# nrf_can.net
KiCad netlist of a schematic drawn in EAGLE
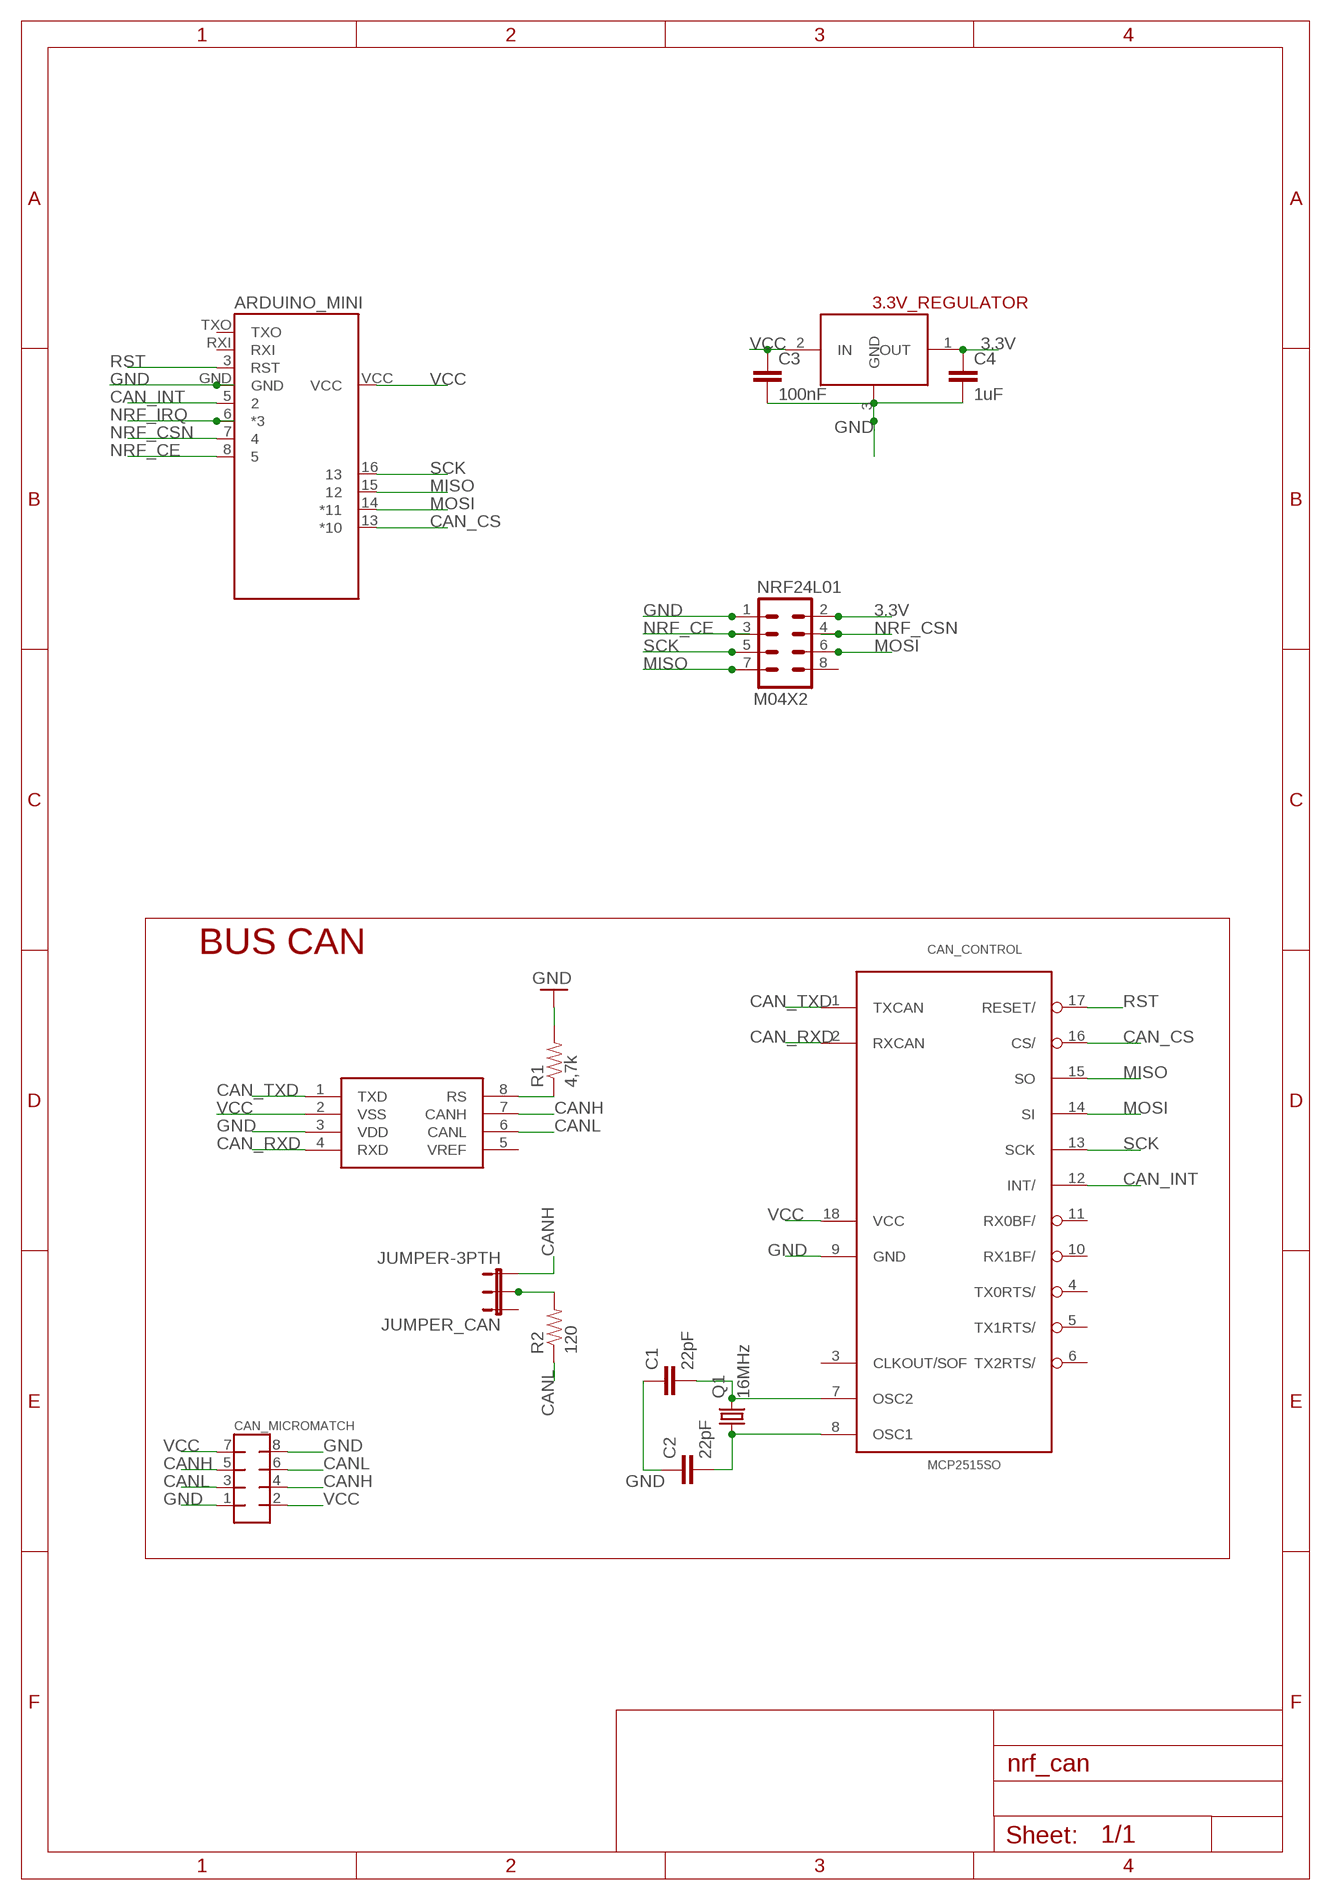
[diagram p0: schematic, sheet 1]

(export (version "E")
  (design (tool "Eeschema 10.0.6"))
  (components
    (comp (ref "3.3V_REGULATOR")
      (value "LM3480IM4")
      (footprint "eagle-import:SOT23-3")
      (libsource (lib "eagle-import") (part "LM3480IM4"))
    )
    (comp (ref "ARDUINO_MINI")
      (value "ARDUINO_PRO_MININRF24L01")
      (footprint "eagle-import:ARDUINO_PRO_MINI")
      (libsource (lib "eagle-import") (part "ARDUINO_PRO_MININRF24L01"))
    )
    (comp (ref "C1")
      (value "22pF")
      (footprint "eagle-import:0805")
      (libsource (lib "eagle-import") (part "CAP0805"))
    )
    (comp (ref "C2")
      (value "22pF")
      (footprint "eagle-import:0805")
      (libsource (lib "eagle-import") (part "CAP0805"))
    )
    (comp (ref "C3")
      (value "100nF")
      (footprint "eagle-import:0805")
      (libsource (lib "eagle-import") (part "CAP0805"))
    )
    (comp (ref "C4")
      (value "1uF")
      (footprint "eagle-import:0805")
      (libsource (lib "eagle-import") (part "CAP0805"))
    )
    (comp (ref "CAN_CONTROL")
      (value "MCP2515SO")
      (footprint "eagle-import:SO18L")
      (libsource (lib "eagle-import") (part "MCP2515SO"))
    )
    (comp (ref "CAN_MICROMATCH")
      (value "MMATCH-8-PTH")
      (footprint "eagle-import:AMP-215079-8")
      (libsource (lib "eagle-import") (part "MMATCH-8-PTH"))
    )
    (comp (ref "JUMPER_CAN")
      (value "JUMPER-3PTH")
      (footprint "eagle-import:1X03")
      (libsource (lib "eagle-import") (part "JUMPER-3PTH"))
    )
    (comp (ref "NRF24L01")
      (value "M04X2")
      (footprint "eagle-import:2X4")
      (libsource (lib "eagle-import") (part "M04X2"))
    )
    (comp (ref "Q1")
      (value "16MHz")
      (footprint "eagle-import:HC49_S")
      (libsource (lib "eagle-import") (part "CRYSTALHC49S"))
    )
    (comp (ref "R1")
      (value "4,7k")
      (footprint "eagle-import:0805")
      (libsource (lib "eagle-import") (part "RESISTOR0805-RES"))
    )
    (comp (ref "R2")
      (value "120")
      (footprint "eagle-import:0805")
      (libsource (lib "eagle-import") (part "RESISTOR0805-RES"))
    )
    (comp (ref "TRANSCEIVER")
      (value "MCP2551")
      (footprint "eagle-import:SO08")
      (libsource (lib "eagle-import") (part "MCP2551"))
    )
  )
  (nets
    (net (code "1") (name "/3.3V") (class "Default")
      (node (ref "3.3V_REGULATOR") (pin "1") (pinfunction "OUT_1") (pintype "bidirectional"))
      (node (ref "C4") (pin "1") (pinfunction "1_1") (pintype "passive"))
      (node (ref "NRF24L01") (pin "2") (pinfunction "2_2") (pintype "passive"))
    )
    (net (code "2") (name "/CANH") (class "Default")
      (node (ref "CAN_MICROMATCH") (pin "4") (pinfunction "4_4") (pintype "bidirectional"))
      (node (ref "CAN_MICROMATCH") (pin "5") (pinfunction "5_5") (pintype "bidirectional"))
      (node (ref "JUMPER_CAN") (pin "3") (pinfunction "3_3") (pintype "passive"))
      (node (ref "TRANSCEIVER") (pin "7") (pinfunction "CANH_7") (pintype "bidirectional"))
    )
    (net (code "3") (name "/CANL") (class "Default")
      (node (ref "CAN_MICROMATCH") (pin "3") (pinfunction "3_3") (pintype "bidirectional"))
      (node (ref "CAN_MICROMATCH") (pin "6") (pinfunction "6_6") (pintype "bidirectional"))
      (node (ref "R2") (pin "1") (pinfunction "1_1") (pintype "passive"))
      (node (ref "TRANSCEIVER") (pin "6") (pinfunction "CANL_6") (pintype "bidirectional"))
    )
    (net (code "4") (name "/CAN_CS") (class "Default")
      (node (ref "ARDUINO_MINI") (pin "13") (pinfunction "*10_13") (pintype "bidirectional"))
      (node (ref "CAN_CONTROL") (pin "16") (pinfunction "CS/_16") (pintype "input"))
    )
    (net (code "5") (name "/CAN_INT") (class "Default")
      (node (ref "ARDUINO_MINI") (pin "5") (pinfunction "2_5") (pintype "bidirectional"))
      (node (ref "CAN_CONTROL") (pin "12") (pinfunction "INT/_12") (pintype "output"))
    )
    (net (code "6") (name "/CAN_RXD") (class "Default")
      (node (ref "CAN_CONTROL") (pin "2") (pinfunction "RXCAN_2") (pintype "input"))
      (node (ref "TRANSCEIVER") (pin "4") (pinfunction "RXD_4") (pintype "bidirectional"))
    )
    (net (code "7") (name "/CAN_TXD") (class "Default")
      (node (ref "CAN_CONTROL") (pin "1") (pinfunction "TXCAN_1") (pintype "output"))
      (node (ref "TRANSCEIVER") (pin "1") (pinfunction "TXD_1") (pintype "bidirectional"))
    )
    (net (code "8") (name "/MISO") (class "Default")
      (node (ref "ARDUINO_MINI") (pin "15") (pinfunction "12_15") (pintype "bidirectional"))
      (node (ref "CAN_CONTROL") (pin "15") (pinfunction "SO_15") (pintype "output"))
      (node (ref "NRF24L01") (pin "7") (pinfunction "7_7") (pintype "passive"))
    )
    (net (code "9") (name "/MOSI") (class "Default")
      (node (ref "ARDUINO_MINI") (pin "14") (pinfunction "*11_14") (pintype "bidirectional"))
      (node (ref "CAN_CONTROL") (pin "14") (pinfunction "SI_14") (pintype "input"))
      (node (ref "NRF24L01") (pin "6") (pinfunction "6_6") (pintype "passive"))
    )
    (net (code "10") (name "/NRF_CE") (class "Default")
      (node (ref "ARDUINO_MINI") (pin "8") (pinfunction "5_8") (pintype "bidirectional"))
      (node (ref "NRF24L01") (pin "3") (pinfunction "3_3") (pintype "passive"))
    )
    (net (code "11") (name "/NRF_CSN") (class "Default")
      (node (ref "ARDUINO_MINI") (pin "7") (pinfunction "4_7") (pintype "bidirectional"))
      (node (ref "NRF24L01") (pin "4") (pinfunction "4_4") (pintype "passive"))
    )
    (net (code "12") (name "/NRF_IRQ") (class "Default")
      (node (ref "ARDUINO_MINI") (pin "6") (pinfunction "*3_6") (pintype "bidirectional"))
    )
    (net (code "13") (name "/RST") (class "Default")
      (node (ref "ARDUINO_MINI") (pin "3") (pinfunction "RST_3") (pintype "bidirectional"))
      (node (ref "CAN_CONTROL") (pin "17") (pinfunction "RESET/_17") (pintype "input"))
    )
    (net (code "14") (name "/SCK") (class "Default")
      (node (ref "ARDUINO_MINI") (pin "16") (pinfunction "13_16") (pintype "bidirectional"))
      (node (ref "CAN_CONTROL") (pin "13") (pinfunction "SCK_13") (pintype "input"))
      (node (ref "NRF24L01") (pin "5") (pinfunction "5_5") (pintype "passive"))
    )
    (net (code "15") (name "/VCC") (class "Default")
      (node (ref "3.3V_REGULATOR") (pin "2") (pinfunction "IN_2") (pintype "bidirectional"))
      (node (ref "ARDUINO_MINI") (pin "VCC") (pinfunction "VCC_VCC") (pintype "bidirectional"))
      (node (ref "C3") (pin "1") (pinfunction "1_1") (pintype "passive"))
      (node (ref "CAN_CONTROL") (pin "18") (pinfunction "VCC_18") (pintype "power_in"))
      (node (ref "CAN_MICROMATCH") (pin "2") (pinfunction "2_2") (pintype "bidirectional"))
      (node (ref "CAN_MICROMATCH") (pin "7") (pinfunction "7_7") (pintype "bidirectional"))
      (node (ref "TRANSCEIVER") (pin "2") (pinfunction "VSS_2") (pintype "bidirectional"))
    )
    (net (code "16") (name "GND") (class "Default")
      (node (ref "3.3V_REGULATOR") (pin "3") (pinfunction "GND_3") (pintype "bidirectional"))
      (node (ref "ARDUINO_MINI") (pin "GND") (pinfunction "GND_GND") (pintype "bidirectional"))
      (node (ref "C1") (pin "1") (pinfunction "1_1") (pintype "passive"))
      (node (ref "C2") (pin "1") (pinfunction "1_1") (pintype "passive"))
      (node (ref "C3") (pin "2") (pinfunction "2_2") (pintype "passive"))
      (node (ref "C4") (pin "2") (pinfunction "2_2") (pintype "passive"))
      (node (ref "CAN_CONTROL") (pin "9") (pinfunction "GND_9") (pintype "power_in"))
      (node (ref "CAN_MICROMATCH") (pin "1") (pinfunction "1_1") (pintype "bidirectional"))
      (node (ref "CAN_MICROMATCH") (pin "8") (pinfunction "8_8") (pintype "bidirectional"))
      (node (ref "NRF24L01") (pin "1") (pinfunction "1_1") (pintype "passive"))
      (node (ref "R1") (pin "2") (pinfunction "2_2") (pintype "passive"))
      (node (ref "TRANSCEIVER") (pin "3") (pinfunction "VDD_3") (pintype "bidirectional"))
    )
    (net (code "17") (name "Net-(CAN_CONTROL-OSC1)") (class "Default")
      (node (ref "C2") (pin "2") (pinfunction "2_2") (pintype "passive"))
      (node (ref "CAN_CONTROL") (pin "8") (pinfunction "OSC1_8") (pintype "bidirectional"))
      (node (ref "Q1") (pin "1") (pinfunction "1_1") (pintype "passive"))
    )
    (net (code "18") (name "Net-(CAN_CONTROL-OSC2)") (class "Default")
      (node (ref "C1") (pin "2") (pinfunction "2_2") (pintype "passive"))
      (node (ref "CAN_CONTROL") (pin "7") (pinfunction "OSC2_7") (pintype "bidirectional"))
      (node (ref "Q1") (pin "2") (pinfunction "2_2") (pintype "passive"))
    )
    (net (code "19") (name "Net-(JUMPER_CAN-Pad2)") (class "Default")
      (node (ref "JUMPER_CAN") (pin "2") (pinfunction "2_2") (pintype "passive"))
      (node (ref "R2") (pin "2") (pinfunction "2_2") (pintype "passive"))
    )
    (net (code "20") (name "Net-(TRANSCEIVER-RS)") (class "Default")
      (node (ref "R1") (pin "1") (pinfunction "1_1") (pintype "passive"))
      (node (ref "TRANSCEIVER") (pin "8") (pinfunction "RS_8") (pintype "bidirectional"))
    )
    (net (code "21") (name "unconnected-(ARDUINO_MINI-PadRXI)") (class "Default")
      (node (ref "ARDUINO_MINI") (pin "RXI") (pinfunction "RXI_RXI") (pintype "bidirectional"))
    )
    (net (code "22") (name "unconnected-(ARDUINO_MINI-PadTXO)") (class "Default")
      (node (ref "ARDUINO_MINI") (pin "TXO") (pinfunction "TXO_TXO") (pintype "bidirectional"))
    )
    (net (code "23") (name "unconnected-(CAN_CONTROL-CLKOUT{slash}SOF-Pad3)") (class "Default")
      (node (ref "CAN_CONTROL") (pin "3") (pinfunction "CLKOUT/SOF_3") (pintype "bidirectional"))
    )
    (net (code "24") (name "unconnected-(CAN_CONTROL-RX0BF{slash}-Pad11)") (class "Default")
      (node (ref "CAN_CONTROL") (pin "11") (pinfunction "RX0BF/_11") (pintype "bidirectional"))
    )
    (net (code "25") (name "unconnected-(CAN_CONTROL-RX1BF{slash}-Pad10)") (class "Default")
      (node (ref "CAN_CONTROL") (pin "10") (pinfunction "RX1BF/_10") (pintype "bidirectional"))
    )
    (net (code "26") (name "unconnected-(CAN_CONTROL-TX0RTS{slash}-Pad4)") (class "Default")
      (node (ref "CAN_CONTROL") (pin "4") (pinfunction "TX0RTS/_4") (pintype "bidirectional"))
    )
    (net (code "27") (name "unconnected-(CAN_CONTROL-TX1RTS{slash}-Pad5)") (class "Default")
      (node (ref "CAN_CONTROL") (pin "5") (pinfunction "TX1RTS/_5") (pintype "bidirectional"))
    )
    (net (code "28") (name "unconnected-(CAN_CONTROL-TX2RTS{slash}-Pad6)") (class "Default")
      (node (ref "CAN_CONTROL") (pin "6") (pinfunction "TX2RTS/_6") (pintype "bidirectional"))
    )
    (net (code "29") (name "unconnected-(JUMPER_CAN-Pad1)") (class "Default")
      (node (ref "JUMPER_CAN") (pin "1") (pinfunction "1_1") (pintype "passive"))
    )
    (net (code "30") (name "unconnected-(NRF24L01-Pad8)") (class "Default")
      (node (ref "NRF24L01") (pin "8") (pinfunction "8_8") (pintype "passive"))
    )
    (net (code "31") (name "unconnected-(TRANSCEIVER-VREF-Pad5)") (class "Default")
      (node (ref "TRANSCEIVER") (pin "5") (pinfunction "VREF_5") (pintype "bidirectional"))
    )
  )
)
